# mahmuduino.net
KiCad netlist of a schematic drawn in EAGLE
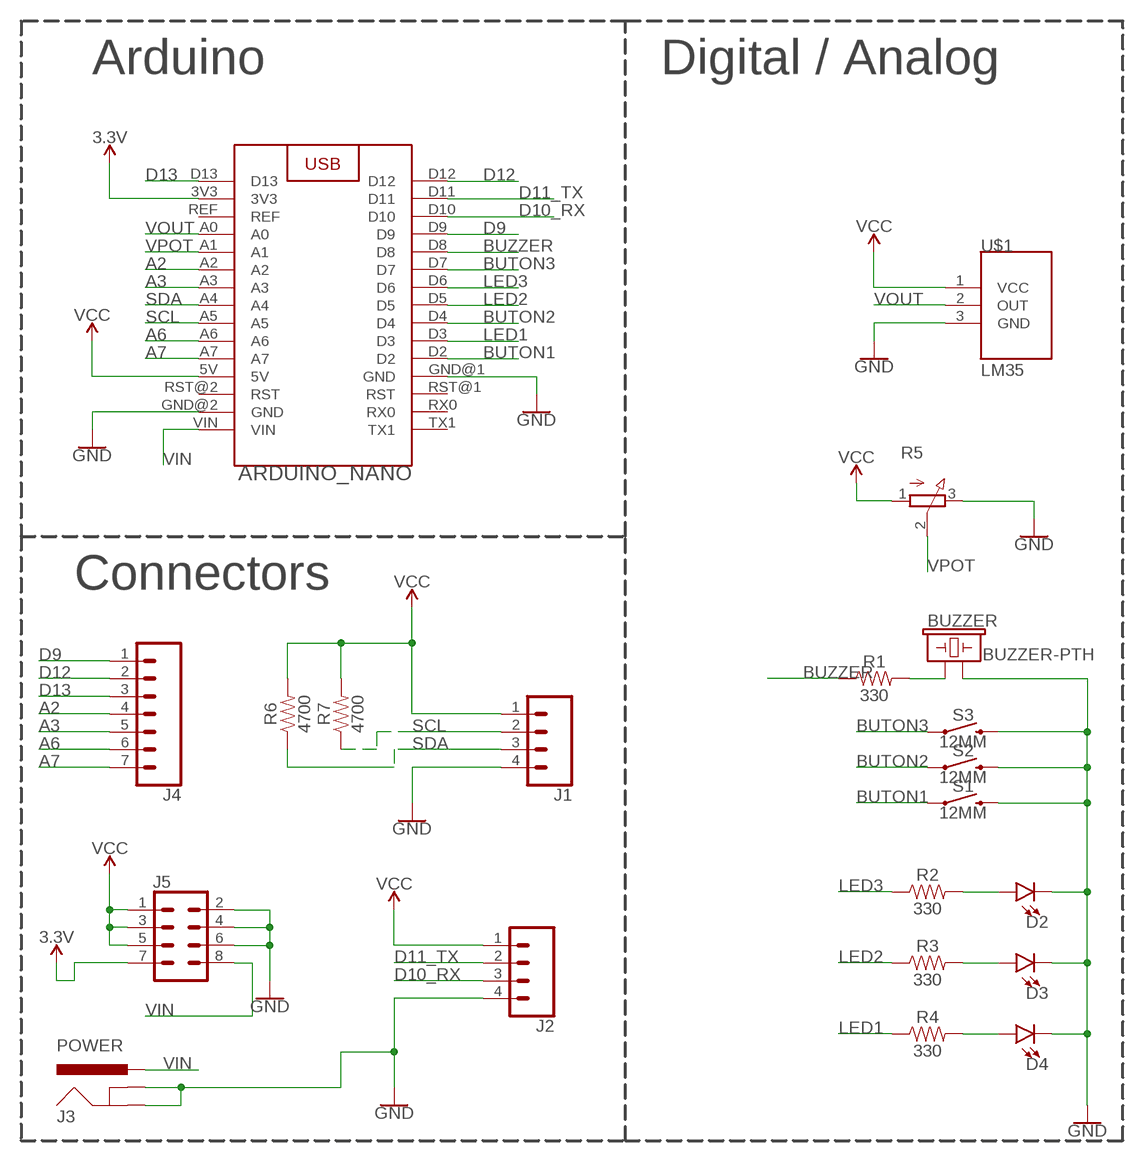
[diagram p0: schematic, sheet 1]

(export (version "E")
  (design (tool "Eeschema 10.0.6"))
  (components
    (comp (ref "ARDUINO_NANO")
      (value "ARDUINO_NANO")
      (footprint "eagle-import:ARDUINO_NANO")
      (libsource (lib "eagle-import") (part "ARDUINO_NANO"))
    )
    (comp (ref "BUZZER")
      (value "BUZZER-PTH")
      (footprint "eagle-import:BUZZER-12MM")
      (libsource (lib "eagle-import") (part "BUZZER-PTH"))
    )
    (comp (ref "D2")
      (value "LED-3MM-NO_SILK")
      (footprint "eagle-import:LED_3MM-NS")
      (libsource (lib "eagle-import") (part "LED-3MM-NO_SILK"))
    )
    (comp (ref "D3")
      (value "LED-3MM-NO_SILK")
      (footprint "eagle-import:LED_3MM-NS")
      (libsource (lib "eagle-import") (part "LED-3MM-NO_SILK"))
    )
    (comp (ref "D4")
      (value "LED-3MM-NO_SILK")
      (footprint "eagle-import:LED_3MM-NS")
      (libsource (lib "eagle-import") (part "LED-3MM-NO_SILK"))
    )
    (comp (ref "J1")
      (value "CONN_04")
      (footprint "eagle-import:1X04")
      (libsource (lib "eagle-import") (part "CONN_04"))
    )
    (comp (ref "J2")
      (value "CONN_04")
      (footprint "eagle-import:1X04")
      (libsource (lib "eagle-import") (part "CONN_04"))
    )
    (comp (ref "J3")
      (value "POWER")
      (footprint "eagle-import:POWER_JACK_PTH")
      (libsource (lib "eagle-import") (part "POWER_JACK"))
    )
    (comp (ref "J4")
      (value "CONN_07")
      (footprint "eagle-import:1X07")
      (libsource (lib "eagle-import") (part "CONN_07"))
    )
    (comp (ref "J5")
      (value "CONN_04X2")
      (footprint "eagle-import:2X4")
      (libsource (lib "eagle-import") (part "CONN_04X2"))
    )
    (comp (ref "R1")
      (value "330")
      (footprint "eagle-import:AXIAL-0.3")
      (libsource (lib "eagle-import") (part "1KOHM-HORIZ-1/4W-5%"))
    )
    (comp (ref "R2")
      (value "330")
      (footprint "eagle-import:AXIAL-0.3")
      (libsource (lib "eagle-import") (part "1KOHM-HORIZ-1/4W-5%"))
    )
    (comp (ref "R3")
      (value "330")
      (footprint "eagle-import:AXIAL-0.3")
      (libsource (lib "eagle-import") (part "1KOHM-HORIZ-1/4W-5%"))
    )
    (comp (ref "R4")
      (value "330")
      (footprint "eagle-import:AXIAL-0.3")
      (libsource (lib "eagle-import") (part "1KOHM-HORIZ-1/4W-5%"))
    )
    (comp (ref "R5")
      (value "3RP/1610N")
      (footprint "eagle-import:3RP_1610N")
      (libsource (lib "eagle-import") (part "3RP/1610N"))
    )
    (comp (ref "R6")
      (value "4700")
      (footprint "eagle-import:AXIAL-0.3")
      (libsource (lib "eagle-import") (part "1KOHM-HORIZ-1/4W-5%"))
    )
    (comp (ref "R7")
      (value "4700")
      (footprint "eagle-import:AXIAL-0.3")
      (libsource (lib "eagle-import") (part "1KOHM-HORIZ-1/4W-5%"))
    )
    (comp (ref "S1")
      (value "12MM")
      (footprint "eagle-import:TACTILE_SWITCH_PTH_12MM")
      (libsource (lib "eagle-import") (part "MOMENTARY-SWITCH-SPST-PTH-12MM"))
    )
    (comp (ref "S2")
      (value "12MM")
      (footprint "eagle-import:TACTILE_SWITCH_PTH_12MM")
      (libsource (lib "eagle-import") (part "MOMENTARY-SWITCH-SPST-PTH-12MM"))
    )
    (comp (ref "S3")
      (value "12MM")
      (footprint "eagle-import:TACTILE_SWITCH_PTH_12MM")
      (libsource (lib "eagle-import") (part "MOMENTARY-SWITCH-SPST-PTH-12MM"))
    )
    (comp (ref "U$1")
      (value "LM35")
      (footprint "eagle-import:TO-92")
      (libsource (lib "eagle-import") (part "LM35"))
    )
  )
  (nets
    (net (code "1") (name "/A2") (class "Default")
      (node (ref "ARDUINO_NANO") (pin "A2") (pinfunction "A2_A2") (pintype "bidirectional"))
      (node (ref "J4") (pin "4") (pinfunction "4_4") (pintype "passive"))
    )
    (net (code "2") (name "/A3") (class "Default")
      (node (ref "ARDUINO_NANO") (pin "A3") (pinfunction "A3_A3") (pintype "bidirectional"))
      (node (ref "J4") (pin "5") (pinfunction "5_5") (pintype "passive"))
    )
    (net (code "3") (name "/A6") (class "Default")
      (node (ref "ARDUINO_NANO") (pin "A6") (pinfunction "A6_A6") (pintype "bidirectional"))
      (node (ref "J4") (pin "6") (pinfunction "6_6") (pintype "passive"))
    )
    (net (code "4") (name "/A7") (class "Default")
      (node (ref "ARDUINO_NANO") (pin "A7") (pinfunction "A7_A7") (pintype "bidirectional"))
      (node (ref "J4") (pin "7") (pinfunction "7_7") (pintype "passive"))
    )
    (net (code "5") (name "/BUTON1") (class "Default")
      (node (ref "ARDUINO_NANO") (pin "D2") (pinfunction "D2_D2") (pintype "bidirectional"))
      (node (ref "S1") (pin "1") (pinfunction "1_1") (pintype "passive"))
    )
    (net (code "6") (name "/BUTON2") (class "Default")
      (node (ref "ARDUINO_NANO") (pin "D4") (pinfunction "D4_D4") (pintype "bidirectional"))
      (node (ref "S2") (pin "1") (pinfunction "1_1") (pintype "passive"))
    )
    (net (code "7") (name "/BUTON3") (class "Default")
      (node (ref "ARDUINO_NANO") (pin "D7") (pinfunction "D7_D7") (pintype "bidirectional"))
      (node (ref "S3") (pin "1") (pinfunction "1_1") (pintype "passive"))
    )
    (net (code "8") (name "/BUZZER") (class "Default")
      (node (ref "ARDUINO_NANO") (pin "D8") (pinfunction "D8_D8") (pintype "bidirectional"))
      (node (ref "R1") (pin "P$1") (pinfunction "1_P$1") (pintype "passive"))
    )
    (net (code "9") (name "/D9") (class "Default")
      (node (ref "ARDUINO_NANO") (pin "D9") (pinfunction "D9_D9") (pintype "bidirectional"))
      (node (ref "J4") (pin "1") (pinfunction "1_1") (pintype "passive"))
    )
    (net (code "10") (name "/D10_RX") (class "Default")
      (node (ref "ARDUINO_NANO") (pin "D10") (pinfunction "D10_D10") (pintype "bidirectional"))
      (node (ref "J2") (pin "3") (pinfunction "3_3") (pintype "passive"))
    )
    (net (code "11") (name "/D11_TX") (class "Default")
      (node (ref "ARDUINO_NANO") (pin "D11") (pinfunction "D11_D11") (pintype "bidirectional"))
      (node (ref "J2") (pin "2") (pinfunction "2_2") (pintype "passive"))
    )
    (net (code "12") (name "/D12") (class "Default")
      (node (ref "ARDUINO_NANO") (pin "D12") (pinfunction "D12_D12") (pintype "bidirectional"))
      (node (ref "J4") (pin "2") (pinfunction "2_2") (pintype "passive"))
    )
    (net (code "13") (name "/D13") (class "Default")
      (node (ref "ARDUINO_NANO") (pin "D13") (pinfunction "D13_D13") (pintype "bidirectional"))
      (node (ref "J4") (pin "3") (pinfunction "3_3") (pintype "passive"))
    )
    (net (code "14") (name "/LED1") (class "Default")
      (node (ref "ARDUINO_NANO") (pin "D3") (pinfunction "D3_D3") (pintype "bidirectional"))
      (node (ref "R4") (pin "P$1") (pinfunction "1_P$1") (pintype "passive"))
    )
    (net (code "15") (name "/LED2") (class "Default")
      (node (ref "ARDUINO_NANO") (pin "D5") (pinfunction "D5_D5") (pintype "bidirectional"))
      (node (ref "R3") (pin "P$1") (pinfunction "1_P$1") (pintype "passive"))
    )
    (net (code "16") (name "/LED3") (class "Default")
      (node (ref "ARDUINO_NANO") (pin "D6") (pinfunction "D6_D6") (pintype "bidirectional"))
      (node (ref "R2") (pin "P$1") (pinfunction "1_P$1") (pintype "passive"))
    )
    (net (code "17") (name "/SCL") (class "Default")
      (node (ref "ARDUINO_NANO") (pin "A5") (pinfunction "A5_A5") (pintype "bidirectional"))
      (node (ref "J1") (pin "2") (pinfunction "2_2") (pintype "passive"))
      (node (ref "R7") (pin "P$1") (pinfunction "1_P$1") (pintype "passive"))
    )
    (net (code "18") (name "/SDA") (class "Default")
      (node (ref "ARDUINO_NANO") (pin "A4") (pinfunction "A4_A4") (pintype "bidirectional"))
      (node (ref "J1") (pin "3") (pinfunction "3_3") (pintype "passive"))
      (node (ref "R6") (pin "P$1") (pinfunction "1_P$1") (pintype "passive"))
    )
    (net (code "19") (name "/VIN") (class "Default")
      (node (ref "ARDUINO_NANO") (pin "VIN") (pinfunction "VIN_VIN") (pintype "bidirectional"))
      (node (ref "J3") (pin "PWR") (pinfunction "PWR_PWR") (pintype "bidirectional"))
      (node (ref "J5") (pin "8") (pinfunction "8_8") (pintype "passive"))
    )
    (net (code "20") (name "/VOUT") (class "Default")
      (node (ref "ARDUINO_NANO") (pin "A0") (pinfunction "A0_A0") (pintype "bidirectional"))
      (node (ref "U$1") (pin "2") (pinfunction "OUT_2") (pintype "bidirectional"))
    )
    (net (code "21") (name "/VPOT") (class "Default")
      (node (ref "ARDUINO_NANO") (pin "A1") (pinfunction "A1_A1") (pintype "bidirectional"))
      (node (ref "R5") (pin "2") (pinfunction "S_2") (pintype "passive"))
    )
    (net (code "22") (name "3.3V") (class "Default")
      (node (ref "ARDUINO_NANO") (pin "3V3") (pinfunction "3V3_3V3") (pintype "bidirectional"))
      (node (ref "J5") (pin "7") (pinfunction "7_7") (pintype "passive"))
    )
    (net (code "23") (name "GND") (class "Default")
      (node (ref "ARDUINO_NANO") (pin "GND@1") (pinfunction "GND_GND@1") (pintype "bidirectional"))
      (node (ref "ARDUINO_NANO") (pin "GND@2") (pinfunction "GND_GND@2") (pintype "bidirectional"))
      (node (ref "BUZZER") (pin "-") (pinfunction "2_-") (pintype "passive"))
      (node (ref "D2") (pin "K") (pinfunction "C_K") (pintype "passive"))
      (node (ref "D3") (pin "K") (pinfunction "C_K") (pintype "passive"))
      (node (ref "D4") (pin "K") (pinfunction "C_K") (pintype "passive"))
      (node (ref "J1") (pin "4") (pinfunction "4_4") (pintype "passive"))
      (node (ref "J2") (pin "4") (pinfunction "4_4") (pintype "passive"))
      (node (ref "J3") (pin "GND") (pinfunction "GND_GND") (pintype "bidirectional"))
      (node (ref "J3") (pin "GNDBREAK") (pinfunction "GNDBREAK_GNDBREAK") (pintype "bidirectional"))
      (node (ref "J5") (pin "2") (pinfunction "2_2") (pintype "passive"))
      (node (ref "J5") (pin "4") (pinfunction "4_4") (pintype "passive"))
      (node (ref "J5") (pin "6") (pinfunction "6_6") (pintype "passive"))
      (node (ref "R5") (pin "3") (pinfunction "E_3") (pintype "passive"))
      (node (ref "S1") (pin "3") (pinfunction "2_3") (pintype "passive"))
      (node (ref "S2") (pin "3") (pinfunction "2_3") (pintype "passive"))
      (node (ref "S3") (pin "3") (pinfunction "2_3") (pintype "passive"))
      (node (ref "U$1") (pin "3") (pinfunction "GND_3") (pintype "bidirectional"))
    )
    (net (code "24") (name "Net-(BUZZER-1)") (class "Default")
      (node (ref "BUZZER") (pin "+") (pinfunction "1_+") (pintype "passive"))
      (node (ref "R1") (pin "P$2") (pinfunction "2_P$2") (pintype "passive"))
    )
    (net (code "25") (name "Net-(R2-2)") (class "Default")
      (node (ref "D2") (pin "A") (pinfunction "A_A") (pintype "passive"))
      (node (ref "R2") (pin "P$2") (pinfunction "2_P$2") (pintype "passive"))
    )
    (net (code "26") (name "Net-(R3-2)") (class "Default")
      (node (ref "D3") (pin "A") (pinfunction "A_A") (pintype "passive"))
      (node (ref "R3") (pin "P$2") (pinfunction "2_P$2") (pintype "passive"))
    )
    (net (code "27") (name "Net-(R4-2)") (class "Default")
      (node (ref "D4") (pin "A") (pinfunction "A_A") (pintype "passive"))
      (node (ref "R4") (pin "P$2") (pinfunction "2_P$2") (pintype "passive"))
    )
    (net (code "28") (name "VCC") (class "Default")
      (node (ref "ARDUINO_NANO") (pin "5V") (pinfunction "5V_5V") (pintype "bidirectional"))
      (node (ref "J1") (pin "1") (pinfunction "1_1") (pintype "passive"))
      (node (ref "J2") (pin "1") (pinfunction "1_1") (pintype "passive"))
      (node (ref "J5") (pin "1") (pinfunction "1_1") (pintype "passive"))
      (node (ref "J5") (pin "3") (pinfunction "3_3") (pintype "passive"))
      (node (ref "J5") (pin "5") (pinfunction "5_5") (pintype "passive"))
      (node (ref "R5") (pin "1") (pinfunction "A_1") (pintype "passive"))
      (node (ref "R6") (pin "P$2") (pinfunction "2_P$2") (pintype "passive"))
      (node (ref "R7") (pin "P$2") (pinfunction "2_P$2") (pintype "passive"))
      (node (ref "U$1") (pin "1") (pinfunction "VCC_1") (pintype "bidirectional"))
    )
    (net (code "29") (name "unconnected-(ARDUINO_NANO-PadREF)") (class "Default")
      (node (ref "ARDUINO_NANO") (pin "REF") (pinfunction "REF_REF") (pintype "bidirectional"))
    )
    (net (code "30") (name "unconnected-(ARDUINO_NANO-PadRX0)") (class "Default")
      (node (ref "ARDUINO_NANO") (pin "RX0") (pinfunction "RX0_RX0") (pintype "bidirectional"))
    )
    (net (code "31") (name "unconnected-(ARDUINO_NANO-PadTX1)") (class "Default")
      (node (ref "ARDUINO_NANO") (pin "TX1") (pinfunction "TX1_TX1") (pintype "bidirectional"))
    )
    (net (code "32") (name "unconnected-(ARDUINO_NANO-RST-PadRST@1)") (class "Default")
      (node (ref "ARDUINO_NANO") (pin "RST@1") (pinfunction "RST_RST@1") (pintype "bidirectional"))
    )
    (net (code "33") (name "unconnected-(ARDUINO_NANO-RST-PadRST@2)") (class "Default")
      (node (ref "ARDUINO_NANO") (pin "RST@2") (pinfunction "RST_RST@2") (pintype "bidirectional"))
    )
  )
)
